# power_supply.net
KiCad netlist of a schematic drawn in Altium Designer
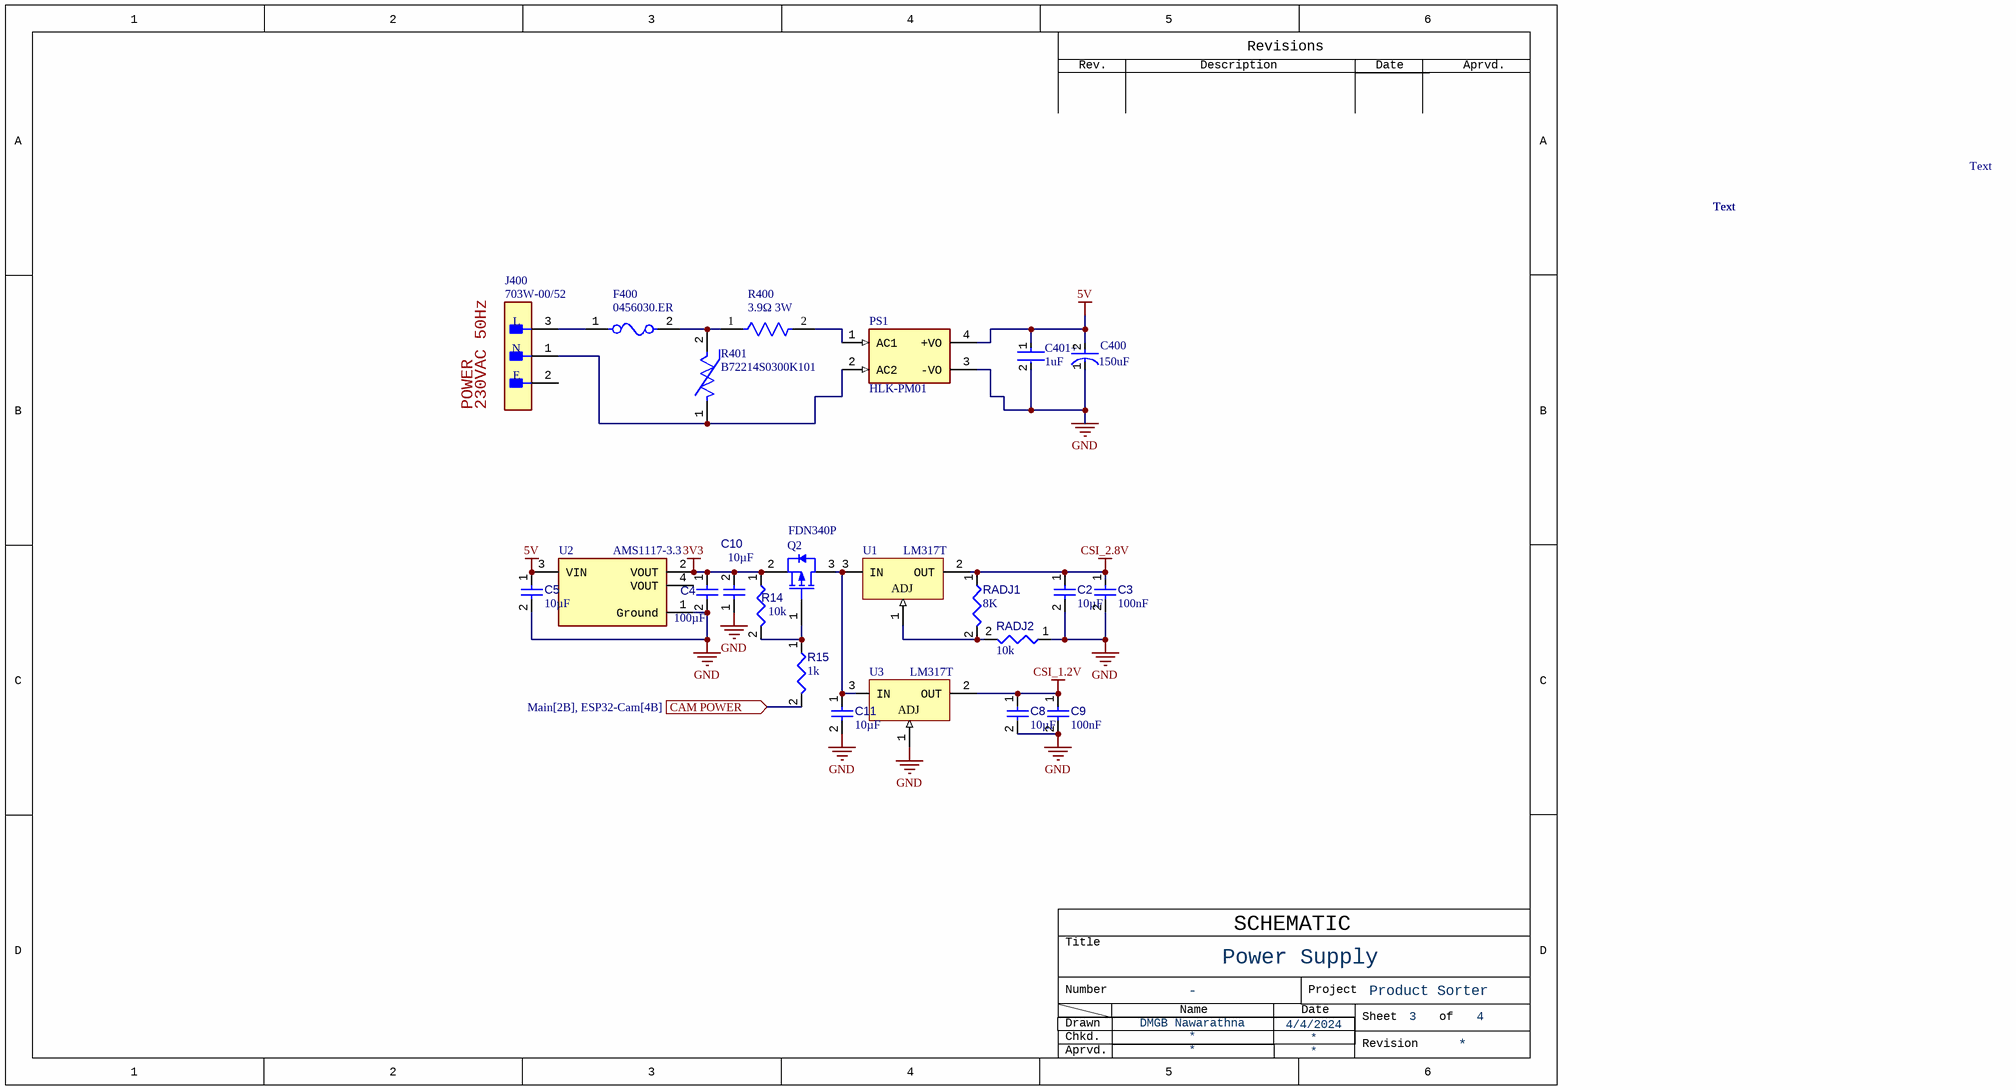
[diagram p0: power supply.SchDoc]

(export (version "E")
  (design (tool "Eeschema 10.0.6"))
  (components
    (comp (ref "C2")
      (value "10µF")
      (footprint "CAPC0603(1608)100_L")
      (description "Chip Capacitor, 10µF +/-20%, 10V, 0603, Thickness 1 mm")
      (fields (field (name "TOLERANCE") "10%") (field (name "Comment") "Capacitor 10µF +/-20% 10V 0603"))
      (libsource (lib "Bimsara Nawarathna") (part "CAP-NP-2"))
    )
    (comp (ref "C3")
      (value "100nF")
      (footprint "CAPC1005X56X25LL10T15")
      (description "Chip Capacitor, 0.1 uF, +/- 5%, 16 V, 0402 (1005 Metric)")
      (fields (field (name "TOLERANCE") "5%") (field (name "Comment") "Capacitor 0.1 uF +/- 5% 16 V 0402"))
      (libsource (lib "Bimsara Nawarathna") (part "CAP-NP-2"))
    )
    (comp (ref "C4")
      (value "100µF")
      (footprint "CAPC0805(2012)145_L")
      (description "Chip Capacitor, 100µF +/-20%, 6.3V, 0805, Thickness 1.45 mm")
      (fields (field (name "TOLERANCE") "10%") (field (name "Comment") "Capacitor 100µF +/-20% 6.3V 0805"))
      (libsource (lib "Bimsara Nawarathna") (part "CAP-NP-2"))
    )
    (comp (ref "C5")
      (value "10µF")
      (footprint "CAPC0603(1608)100_L")
      (description "Chip Capacitor, 10µF +/-20%, 10V, 0603, Thickness 1 mm")
      (fields (field (name "TOLERANCE") "10%") (field (name "Comment") "Capacitor 10µF +/-20% 10V 0603"))
      (libsource (lib "Bimsara Nawarathna") (part "CAP-NP-2"))
    )
    (comp (ref "C8")
      (value "10µF")
      (footprint "CAPC0603(1608)100_L")
      (description "Chip Capacitor, 10µF +/-20%, 10V, 0603, Thickness 1 mm")
      (fields (field (name "TOLERANCE") "10%") (field (name "Comment") "Capacitor 10µF +/-20% 10V 0603"))
      (libsource (lib "Bimsara Nawarathna") (part "CAP-NP-2"))
    )
    (comp (ref "C9")
      (value "100nF")
      (footprint "CAPC1005X56X25LL10T15")
      (description "Chip Capacitor, 0.1 uF, +/- 5%, 16 V, 0402 (1005 Metric)")
      (fields (field (name "TOLERANCE") "5%") (field (name "Comment") "Capacitor 0.1 uF +/- 5% 16 V 0402"))
      (libsource (lib "Bimsara Nawarathna") (part "CAP-NP-2"))
    )
    (comp (ref "C10")
      (value "10µF")
      (footprint "CAPC0603(1608)100_L")
      (description "Chip Capacitor, 10µF +/-20%, 10V, 0603, Thickness 1 mm")
      (fields (field (name "TOLERANCE") "10%") (field (name "Comment") "Capacitor 10µF +/-20% 10V 0603"))
      (libsource (lib "Bimsara Nawarathna") (part "CAP-NP-2"))
    )
    (comp (ref "C11")
      (value "10µF")
      (footprint "CAPC0603(1608)100_L")
      (description "Chip Capacitor, 10µF +/-20%, 10V, 0603, Thickness 1 mm")
      (fields (field (name "TOLERANCE") "10%") (field (name "Comment") "Capacitor 10µF +/-20% 10V 0603"))
      (libsource (lib "Bimsara Nawarathna") (part "CAP-NP-2"))
    )
    (comp (ref "C400")
      (value "EEE-FK1A151P")
      (footprint "FP-FKD-MFG")
      (description "CAP ALUM 150UF 20% 10V SMD")
      (fields
        (field (name "VOLTAGE") "10V")
        (field (name "TOLERANCE") "20%")
        (field (name "CAPACITANCE") "150uF")
      )
      (libsource (lib "Altium Content Vault") (part "a00bbbee19879c290e62620ae7e47b1"))
    )
    (comp (ref "C401")
      (value "12101C105KAZ2A")
      (footprint "FP-1210-L_3_3_0_4-W_2_5_0-IPC_B")
      (description "General Purpose Ceramic Capacitor, 1210, 1uF, 10%, X7R, 15%, 100V")
      (fields
        (field (name "TOLERANCE") "10%")
        (field (name "VOLTAGE") "100V")
        (field (name "CAPACITANCE") "1uF")
      )
      (libsource (lib "Altium Content Vault") (part "02cd4be3c70576c341d710602a673aa"))
    )
    (comp (ref "F400")
      (value "0456030.ER")
      (footprint "FP-0456-MFG")
      (description "FUSE BOARD MNT 30A 125VAC 72VDC")
      (fields
        (field (name "OCTOPART") "https://octopart.com/0456030.er-littelfuse-7502597")
        (field (name "MANUFACTURER") "Littelfuse")
      )
      (libsource (lib "Altium Content Vault") (part "5bcf9b9f640e542cf0359d10258e979"))
    )
    (comp (ref "J400")
      (value "703W-00/52")
      (footprint "FP-703W-00-52-MFG")
      (description "PWR ENT RCPT IEC320-C14 PNL SLDR")
      (libsource (lib "Altium Content Vault") (part "d3fa5aafac2488dd744475722bda3d4"))
    )
    (comp (ref "PS1")
      (value "HLK-PM01")
      (footprint "CONV_HLK-PM01")
      (fields (field (name "MF") "Hi-link") (field (name "MP") "hlk-pm01"))
      (libsource (lib "HLK-PM01") (part "HLK-PM01"))
    )
    (comp (ref "Q2")
      (value "FDN340P")
      (footprint "FAIR-SSOT3L-3_V")
      (fields (field (name "MANUFACTURER") "Fairchild Semiconductor") (field (name "POWER") "500mW"))
      (libsource (lib "Bimsara Nawarathna") (part "PEMOS-GSD-3"))
    )
    (comp (ref "R14")
      (value "10k")
      (footprint "RESC2013X50X35ML15T15")
      (description "Chip Resistor, 10 KOhm, +/- 1%, 125 mW, -55 to 155 degC, 0805 (2012 Metric)")
      (fields (field (name "TOLERANCE") "1%") (field (name "POWER") "125mW"))
      (libsource (lib "Bimsara Nawarathna") (part "RES-2"))
    )
    (comp (ref "R15")
      (value "1k")
      (footprint "RESC0805(2012)_L")
      (description "Chip Resistor, 1 kOhms, +/-5%, 125 mW, -55 to 155 degC, 0805")
      (fields (field (name "TOLERANCE") "5%") (field (name "POWER") "125mW"))
      (libsource (lib "Bimsara Nawarathna") (part "RES-2"))
    )
    (comp (ref "R400")
      (value "RWM04103R90JR15E1")
      (footprint "FP-RWM0410-MFG")
      (description "RWM04103R90JR15E1 Resistor; Wirewound; Res 3.9 Ohms; Pwr-Rtg 3 W; Tol 5%; Axial; Vitreous Enamel")
      (fields
        (field (name "TOLERANCE") "5%")
        (field (name "POWER RATING") "3W")
        (field (name "RESISTANCE") "3.9Ω")
      )
      (libsource (lib "Altium Content Vault") (part "1029c3af85768c4190bb7ad29bc67b5"))
    )
    (comp (ref "R401")
      (value "B72214S0300K101")
      (footprint "FP-B72214S0300K101-MFG")
      (description "VARISTOR 47V 1KA DISC 14MM")
      (fields
        (field (name "OCTOPART") "https://octopart.com/b72214s0300k101-epcos-11931390")
        (field (name "MANUFACTURER") "EPCOS")
      )
      (libsource (lib "Altium Content Vault") (part "78a88060d5b7b043d6e48adc4284376"))
    )
    (comp (ref "RADJ1")
      (value "8K")
      (footprint "RESC0805(2012)_L")
      (description "Chip Resistor, 1 kOhms, +/-5%, 125 mW, -55 to 155 degC, 0805")
      (fields (field (name "TOLERANCE") "5%") (field (name "POWER") "125mW"))
      (libsource (lib "Bimsara Nawarathna") (part "RES-2"))
    )
    (comp (ref "RADJ2")
      (value "10k")
      (footprint "RESC2013X50X35ML15T15")
      (description "Chip Resistor, 10 KOhm, +/- 1%, 125 mW, -55 to 155 degC, 0805 (2012 Metric)")
      (fields (field (name "TOLERANCE") "1%") (field (name "POWER") "125mW"))
      (libsource (lib "Bimsara Nawarathna") (part "RES-2"))
    )
    (comp (ref "U1")
      (value "LM317T")
      (footprint "TO-220")
      (description "1.5A, 1.2V to 37V Adjustable Voltage Regulator, 3-Pin TO-220")
      (libsource (lib "Altium Content Vault") (part "PM-REG-117-SIL3"))
    )
    (comp (ref "U2")
      (value "AMS1117-3.3")
      (footprint "FP-AMS1117-IPC_C")
      (description "LDO Voltage Regulators 1A, 3.3V")
      (fields
        (field (name "OCTOPART") "https://octopart.com/ams1117-3.3-advanced+monolithic+systems-25899300")
        (field (name "MANUFACTURER") "Advanced Monolithic Systems")
      )
      (libsource (lib "Altium Content Vault") (part "8bdbb5f8e77002000e30dd2845d0354"))
    )
    (comp (ref "U3")
      (value "LM317T")
      (footprint "TO-220")
      (description "1.5A, 1.2V to 37V Adjustable Voltage Regulator, 3-Pin TO-220")
      (libsource (lib "Altium Content Vault") (part "PM-REG-117-SIL3"))
    )
  )
  (nets
    (net (code "1") (name "/CAM POWER") (class "Default")
      (node (ref "R15") (pin "2") (pinfunction "2_2") (pintype "passive"))
    )
    (net (code "2") (name "3V3") (class "Default")
      (node (ref "C10") (pin "2") (pinfunction "2_2") (pintype "passive"))
      (node (ref "C4") (pin "1") (pinfunction "1_1") (pintype "passive"))
      (node (ref "Q2") (pin "2") (pinfunction "SOURCE_2") (pintype "passive"))
      (node (ref "R14") (pin "1") (pinfunction "1_1") (pintype "passive"))
      (node (ref "U2") (pin "2") (pinfunction "VOUT_2") (pintype "passive"))
    )
    (net (code "3") (name "5V") (class "Default")
      (node (ref "C400") (pin "2") (pinfunction "A_2") (pintype "passive"))
      (node (ref "C401") (pin "1") (pinfunction "1_1") (pintype "passive"))
      (node (ref "C5") (pin "1") (pinfunction "1_1") (pintype "passive"))
      (node (ref "PS1") (pin "4") (pinfunction "+VO_4") (pintype "power_in"))
      (node (ref "U2") (pin "3") (pinfunction "VIN_3") (pintype "power_in"))
    )
    (net (code "4") (name "CSI_1.2V") (class "Default")
      (node (ref "C8") (pin "1") (pinfunction "1_1") (pintype "passive"))
      (node (ref "C9") (pin "1") (pinfunction "1_1") (pintype "passive"))
      (node (ref "U3") (pin "2") (pinfunction "OUT_2") (pintype "power_in"))
    )
    (net (code "5") (name "CSI_2.8V") (class "Default")
      (node (ref "C2") (pin "1") (pinfunction "1_1") (pintype "passive"))
      (node (ref "C3") (pin "1") (pinfunction "1_1") (pintype "passive"))
      (node (ref "RADJ1") (pin "1") (pinfunction "1_1") (pintype "passive"))
      (node (ref "U1") (pin "2") (pinfunction "OUT_2") (pintype "power_in"))
    )
    (net (code "6") (name "GND") (class "Default")
      (node (ref "C10") (pin "1") (pinfunction "1_1") (pintype "passive"))
      (node (ref "C11") (pin "2") (pinfunction "2_2") (pintype "passive"))
      (node (ref "C2") (pin "2") (pinfunction "2_2") (pintype "passive"))
      (node (ref "C3") (pin "2") (pinfunction "2_2") (pintype "passive"))
      (node (ref "C4") (pin "2") (pinfunction "2_2") (pintype "passive"))
      (node (ref "C400") (pin "1") (pinfunction "C_1") (pintype "passive"))
      (node (ref "C401") (pin "2") (pinfunction "2_2") (pintype "passive"))
      (node (ref "C5") (pin "2") (pinfunction "2_2") (pintype "passive"))
      (node (ref "C8") (pin "2") (pinfunction "2_2") (pintype "passive"))
      (node (ref "C9") (pin "2") (pinfunction "2_2") (pintype "passive"))
      (node (ref "PS1") (pin "3") (pinfunction "-VO_3") (pintype "power_in"))
      (node (ref "RADJ2") (pin "1") (pinfunction "1_1") (pintype "passive"))
      (node (ref "U2") (pin "1") (pinfunction "Ground_1") (pintype "power_in"))
      (node (ref "U3") (pin "1") (pinfunction "ADJ_1") (pintype "input"))
    )
    (net (code "7") (name "Net-(F400-Pad2)") (class "Default")
      (node (ref "F400") (pin "2") (pinfunction "2_2") (pintype "passive"))
      (node (ref "R400") (pin "1") (pinfunction "1_1") (pintype "passive"))
      (node (ref "R401") (pin "2") (pinfunction "2_2") (pintype "passive"))
    )
    (net (code "8") (name "Net-(J400-L)") (class "Default")
      (node (ref "F400") (pin "1") (pinfunction "1_1") (pintype "passive"))
      (node (ref "J400") (pin "3") (pinfunction "L_3") (pintype "passive"))
    )
    (net (code "9") (name "Net-(J400-N)") (class "Default")
      (node (ref "J400") (pin "1") (pinfunction "N_1") (pintype "passive"))
      (node (ref "PS1") (pin "2") (pinfunction "AC2_2") (pintype "input"))
      (node (ref "R401") (pin "1") (pinfunction "1_1") (pintype "passive"))
    )
    (net (code "10") (name "Net-(PS1-AC1)") (class "Default")
      (node (ref "PS1") (pin "1") (pinfunction "AC1_1") (pintype "input"))
      (node (ref "R400") (pin "2") (pinfunction "2_2") (pintype "passive"))
    )
    (net (code "11") (name "Net-(Q2-DRAIN)") (class "Default")
      (node (ref "C11") (pin "1") (pinfunction "1_1") (pintype "passive"))
      (node (ref "Q2") (pin "3") (pinfunction "DRAIN_3") (pintype "passive"))
      (node (ref "U1") (pin "3") (pinfunction "IN_3") (pintype "power_in"))
      (node (ref "U3") (pin "3") (pinfunction "IN_3") (pintype "power_in"))
    )
    (net (code "12") (name "Net-(Q2-GATE)") (class "Default")
      (node (ref "Q2") (pin "1") (pinfunction "GATE_1") (pintype "passive"))
      (node (ref "R14") (pin "2") (pinfunction "2_2") (pintype "passive"))
      (node (ref "R15") (pin "1") (pinfunction "1_1") (pintype "passive"))
    )
    (net (code "13") (name "Net-(U1-ADJ)") (class "Default")
      (node (ref "RADJ1") (pin "2") (pinfunction "2_2") (pintype "passive"))
      (node (ref "RADJ2") (pin "2") (pinfunction "2_2") (pintype "passive"))
      (node (ref "U1") (pin "1") (pinfunction "ADJ_1") (pintype "input"))
    )
    (net (code "14") (name "unconnected-(J400-E-Pad2)") (class "Default")
      (node (ref "J400") (pin "2") (pinfunction "E_2") (pintype "passive"))
    )
    (net (code "15") (name "unconnected-(U2-VOUT-Pad4)") (class "Default")
      (node (ref "U2") (pin "4") (pinfunction "VOUT_4") (pintype "passive"))
    )
  )
)
